# Power_MCU.net
KiCad netlist of a schematic drawn in Altium Designer
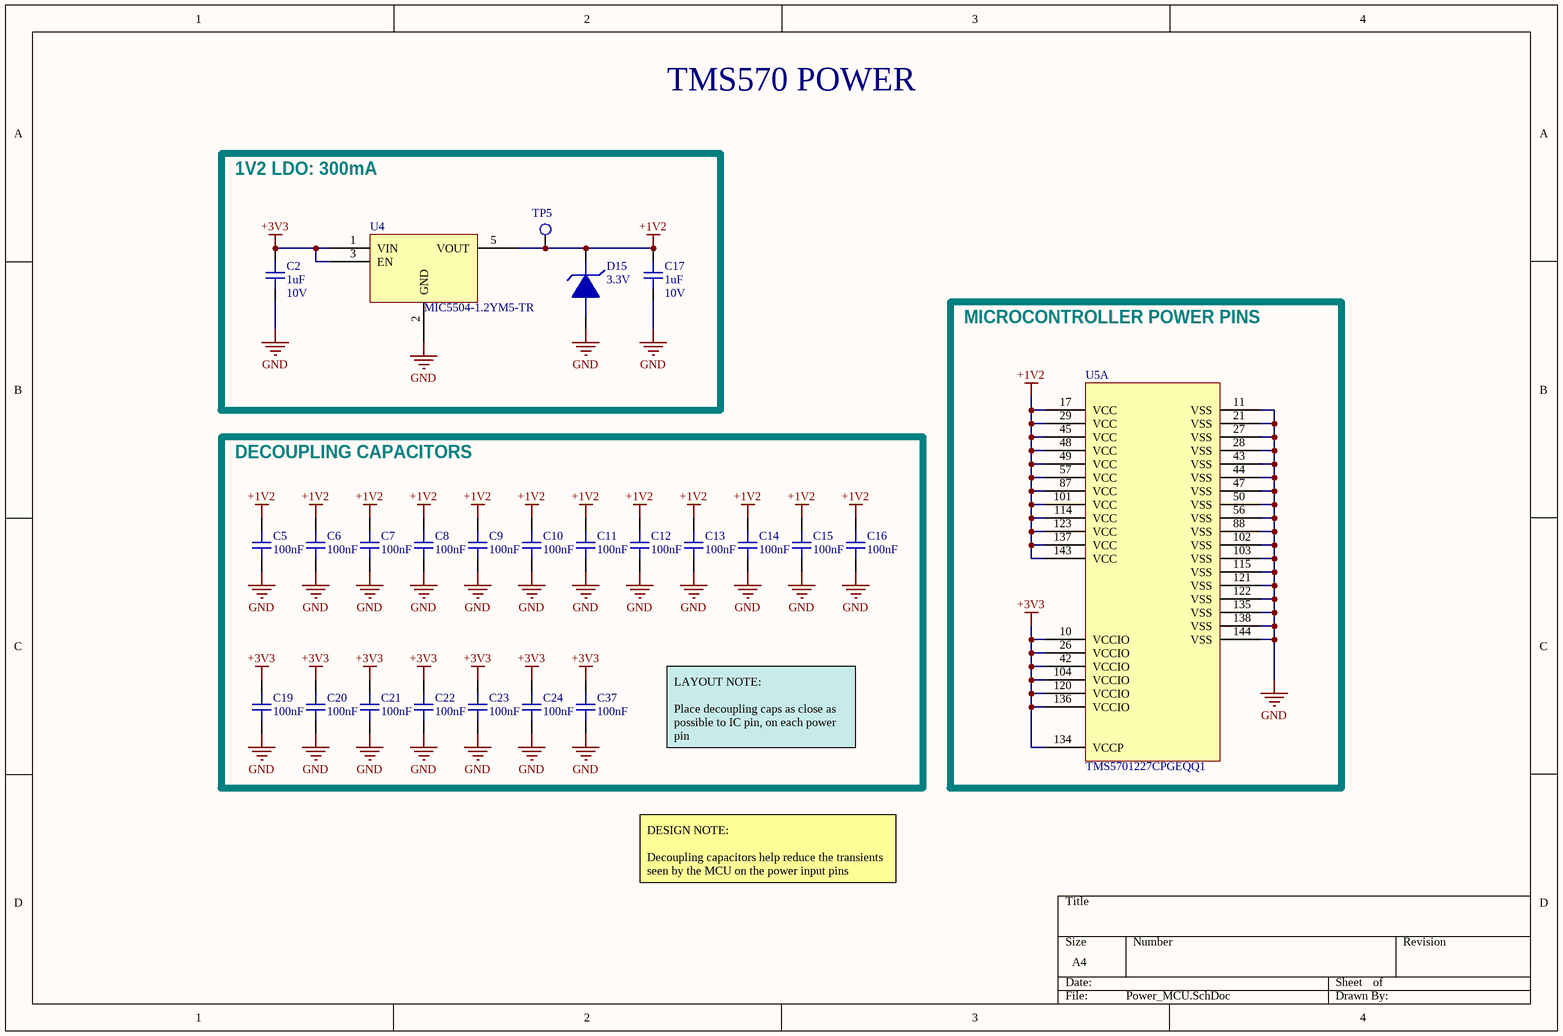
[diagram p0: Power_MCU.SchDoc]

(export (version "E")
  (design (tool "Eeschema 10.0.6"))
  (components
    (comp (ref "C2")
      (value "1uF")
      (footprint "C0402")
      (description "CAP MLCC 1uF 10V 0402 X5R 20% SMD 0402 85C Paper T/R")
      (fields
        (field (name "MANUFACTURER") "Samsung")
        (field (name "MANUFACTURER PART NUMBER") "CL05A105MP5NNNC")
        (field (name "VOLTAGE RATING") "10V")
      )
      (libsource (lib "PHANTOM_LIBRARY") (part "CL05A105MP5NNNC"))
    )
    (comp (ref "C5")
      (value "100nF")
      (footprint "C0402")
      (description "CAP MLCC 0.1uF 10V X5R 0402 20% SMD 0402 85C Paper T/R")
      (fields
        (field (name "MANUFACTURER") "Samsung")
        (field (name "MANUFACTURER PART NUMBER") "CL05A104MP5NNNC")
      )
      (libsource (lib "PHANTOM_LIBRARY") (part "CL05A104MP5NNNC"))
    )
    (comp (ref "C6")
      (value "100nF")
      (footprint "C0402")
      (description "CAP MLCC 0.1uF 10V X5R 0402 20% SMD 0402 85C Paper T/R")
      (fields
        (field (name "MANUFACTURER") "Samsung")
        (field (name "MANUFACTURER PART NUMBER") "CL05A104MP5NNNC")
      )
      (libsource (lib "PHANTOM_LIBRARY") (part "CL05A104MP5NNNC"))
    )
    (comp (ref "C7")
      (value "100nF")
      (footprint "C0402")
      (description "CAP MLCC 0.1uF 10V X5R 0402 20% SMD 0402 85C Paper T/R")
      (fields
        (field (name "MANUFACTURER") "Samsung")
        (field (name "MANUFACTURER PART NUMBER") "CL05A104MP5NNNC")
      )
      (libsource (lib "PHANTOM_LIBRARY") (part "CL05A104MP5NNNC"))
    )
    (comp (ref "C8")
      (value "100nF")
      (footprint "C0402")
      (description "CAP MLCC 0.1uF 10V X5R 0402 20% SMD 0402 85C Paper T/R")
      (fields
        (field (name "MANUFACTURER") "Samsung")
        (field (name "MANUFACTURER PART NUMBER") "CL05A104MP5NNNC")
      )
      (libsource (lib "PHANTOM_LIBRARY") (part "CL05A104MP5NNNC"))
    )
    (comp (ref "C9")
      (value "100nF")
      (footprint "C0402")
      (description "CAP MLCC 0.1uF 10V X5R 0402 20% SMD 0402 85C Paper T/R")
      (fields
        (field (name "MANUFACTURER") "Samsung")
        (field (name "MANUFACTURER PART NUMBER") "CL05A104MP5NNNC")
      )
      (libsource (lib "PHANTOM_LIBRARY") (part "CL05A104MP5NNNC"))
    )
    (comp (ref "C10")
      (value "100nF")
      (footprint "C0402")
      (description "CAP MLCC 0.1uF 10V X5R 0402 20% SMD 0402 85C Paper T/R")
      (fields
        (field (name "MANUFACTURER") "Samsung")
        (field (name "MANUFACTURER PART NUMBER") "CL05A104MP5NNNC")
      )
      (libsource (lib "PHANTOM_LIBRARY") (part "CL05A104MP5NNNC"))
    )
    (comp (ref "C11")
      (value "100nF")
      (footprint "C0402")
      (description "CAP MLCC 0.1uF 10V X5R 0402 20% SMD 0402 85C Paper T/R")
      (fields
        (field (name "MANUFACTURER") "Samsung")
        (field (name "MANUFACTURER PART NUMBER") "CL05A104MP5NNNC")
      )
      (libsource (lib "PHANTOM_LIBRARY") (part "CL05A104MP5NNNC"))
    )
    (comp (ref "C12")
      (value "100nF")
      (footprint "C0402")
      (description "CAP MLCC 0.1uF 10V X5R 0402 20% SMD 0402 85C Paper T/R")
      (fields
        (field (name "MANUFACTURER") "Samsung")
        (field (name "MANUFACTURER PART NUMBER") "CL05A104MP5NNNC")
      )
      (libsource (lib "PHANTOM_LIBRARY") (part "CL05A104MP5NNNC"))
    )
    (comp (ref "C13")
      (value "100nF")
      (footprint "C0402")
      (description "CAP MLCC 0.1uF 10V X5R 0402 20% SMD 0402 85C Paper T/R")
      (fields
        (field (name "MANUFACTURER") "Samsung")
        (field (name "MANUFACTURER PART NUMBER") "CL05A104MP5NNNC")
      )
      (libsource (lib "PHANTOM_LIBRARY") (part "CL05A104MP5NNNC"))
    )
    (comp (ref "C14")
      (value "100nF")
      (footprint "C0402")
      (description "CAP MLCC 0.1uF 10V X5R 0402 20% SMD 0402 85C Paper T/R")
      (fields
        (field (name "MANUFACTURER") "Samsung")
        (field (name "MANUFACTURER PART NUMBER") "CL05A104MP5NNNC")
      )
      (libsource (lib "PHANTOM_LIBRARY") (part "CL05A104MP5NNNC"))
    )
    (comp (ref "C15")
      (value "100nF")
      (footprint "C0402")
      (description "CAP MLCC 0.1uF 10V X5R 0402 20% SMD 0402 85C Paper T/R")
      (fields
        (field (name "MANUFACTURER") "Samsung")
        (field (name "MANUFACTURER PART NUMBER") "CL05A104MP5NNNC")
      )
      (libsource (lib "PHANTOM_LIBRARY") (part "CL05A104MP5NNNC"))
    )
    (comp (ref "C16")
      (value "100nF")
      (footprint "C0402")
      (description "CAP MLCC 0.1uF 10V X5R 0402 20% SMD 0402 85C Paper T/R")
      (fields
        (field (name "MANUFACTURER") "Samsung")
        (field (name "MANUFACTURER PART NUMBER") "CL05A104MP5NNNC")
      )
      (libsource (lib "PHANTOM_LIBRARY") (part "CL05A104MP5NNNC"))
    )
    (comp (ref "C17")
      (value "1uF")
      (footprint "C0402")
      (description "CAP MLCC 1uF 10V 0402 X5R 20% SMD 0402 85C Paper T/R")
      (fields
        (field (name "MANUFACTURER") "Samsung")
        (field (name "MANUFACTURER PART NUMBER") "CL05A105MP5NNNC")
        (field (name "VOLTAGE RATING") "10V")
      )
      (libsource (lib "PHANTOM_LIBRARY") (part "CL05A105MP5NNNC"))
    )
    (comp (ref "C19")
      (value "100nF")
      (footprint "C0402")
      (description "CAP MLCC 0.1uF 10V X5R 0402 20% SMD 0402 85C Paper T/R")
      (fields
        (field (name "MANUFACTURER") "Samsung")
        (field (name "MANUFACTURER PART NUMBER") "CL05A104MP5NNNC")
      )
      (libsource (lib "PHANTOM_LIBRARY") (part "CL05A104MP5NNNC"))
    )
    (comp (ref "C20")
      (value "100nF")
      (footprint "C0402")
      (description "CAP MLCC 0.1uF 10V X5R 0402 20% SMD 0402 85C Paper T/R")
      (fields
        (field (name "MANUFACTURER") "Samsung")
        (field (name "MANUFACTURER PART NUMBER") "CL05A104MP5NNNC")
      )
      (libsource (lib "PHANTOM_LIBRARY") (part "CL05A104MP5NNNC"))
    )
    (comp (ref "C21")
      (value "100nF")
      (footprint "C0402")
      (description "CAP MLCC 0.1uF 10V X5R 0402 20% SMD 0402 85C Paper T/R")
      (fields
        (field (name "MANUFACTURER") "Samsung")
        (field (name "MANUFACTURER PART NUMBER") "CL05A104MP5NNNC")
      )
      (libsource (lib "PHANTOM_LIBRARY") (part "CL05A104MP5NNNC"))
    )
    (comp (ref "C22")
      (value "100nF")
      (footprint "C0402")
      (description "CAP MLCC 0.1uF 10V X5R 0402 20% SMD 0402 85C Paper T/R")
      (fields
        (field (name "MANUFACTURER") "Samsung")
        (field (name "MANUFACTURER PART NUMBER") "CL05A104MP5NNNC")
      )
      (libsource (lib "PHANTOM_LIBRARY") (part "CL05A104MP5NNNC"))
    )
    (comp (ref "C23")
      (value "100nF")
      (footprint "C0402")
      (description "CAP MLCC 0.1uF 10V X5R 0402 20% SMD 0402 85C Paper T/R")
      (fields
        (field (name "MANUFACTURER") "Samsung")
        (field (name "MANUFACTURER PART NUMBER") "CL05A104MP5NNNC")
      )
      (libsource (lib "PHANTOM_LIBRARY") (part "CL05A104MP5NNNC"))
    )
    (comp (ref "C24")
      (value "100nF")
      (footprint "C0402")
      (description "CAP MLCC 0.1uF 10V X5R 0402 20% SMD 0402 85C Paper T/R")
      (fields
        (field (name "MANUFACTURER") "Samsung")
        (field (name "MANUFACTURER PART NUMBER") "CL05A104MP5NNNC")
      )
      (libsource (lib "PHANTOM_LIBRARY") (part "CL05A104MP5NNNC"))
    )
    (comp (ref "C37")
      (value "100nF")
      (footprint "C0402")
      (description "CAP MLCC 0.1uF 10V X5R 0402 20% SMD 0402 85C Paper T/R")
      (fields
        (field (name "MANUFACTURER") "Samsung")
        (field (name "MANUFACTURER PART NUMBER") "CL05A104MP5NNNC")
      )
      (libsource (lib "PHANTOM_LIBRARY") (part "CL05A104MP5NNNC"))
    )
    (comp (ref "D15")
      (value "3.3V")
      (footprint "DIODE_TVS")
      (description "DIODE ZENER 3.3V 1.5W SMA")
      (fields
        (field (name "MANUFACTURER") "ON Semiconductor")
        (field (name "MANUFACTURER PART NUMBER") "1SMA5913BT3G")
      )
      (libsource (lib "PHANTOM_LIBRARY") (part "1SMA5913BT3G"))
    )
    (comp (ref "TP5")
      (value "5015")
      (footprint "TP_HOOK")
      (description "TEST POINT, PCB, SMT")
      (fields (field (name "MANUFACTURER") "Keystone Electronics"))
      (libsource (lib "PHANTOM_LIBRARY") (part "5015"))
    )
    (comp (ref "U4")
      (value "MIC5504-1.2YM5-TR")
      (footprint "SOT23-5-MIC5504")
      (description "IC LDO 1.2V 300mA Enable Pull-Down & Auto Discharge, 5 SOT-23 T/R")
      (fields (field (name "MANUFACTURER") "Microchip"))
      (libsource (lib "PHANTOM_LIBRARY") (part "MIC5504-1.2YM5-TR"))
    )
    (comp (ref "U5")
      (value "TMS5701227CPGEQQ1")
      (footprint "LQFP-144")
      (description "IC MCU 16-Bit/32-Bit Hercules TMS570 ARM Cortex R4F RISC 1280KB Flash 1.2V/3.3V 144-Pin LQFP")
      (fields (field (name "MANUFACTURER") "Texas Instruments"))
      (libsource (lib "PHANTOM_LIBRARY") (part "TMS5701227CPGEQQ1"))
    )
  )
  (nets
    (net (code "1") (name "+1V2") (class "Default")
      (node (ref "C10") (pin "2") (pinfunction "2_2") (pintype "passive"))
      (node (ref "C11") (pin "2") (pinfunction "2_2") (pintype "passive"))
      (node (ref "C12") (pin "2") (pinfunction "2_2") (pintype "passive"))
      (node (ref "C13") (pin "2") (pinfunction "2_2") (pintype "passive"))
      (node (ref "C14") (pin "2") (pinfunction "2_2") (pintype "passive"))
      (node (ref "C15") (pin "2") (pinfunction "2_2") (pintype "passive"))
      (node (ref "C16") (pin "2") (pinfunction "2_2") (pintype "passive"))
      (node (ref "C17") (pin "2") (pinfunction "2_2") (pintype "passive"))
      (node (ref "C5") (pin "2") (pinfunction "2_2") (pintype "passive"))
      (node (ref "C6") (pin "2") (pinfunction "2_2") (pintype "passive"))
      (node (ref "C7") (pin "2") (pinfunction "2_2") (pintype "passive"))
      (node (ref "C8") (pin "2") (pinfunction "2_2") (pintype "passive"))
      (node (ref "C9") (pin "2") (pinfunction "2_2") (pintype "passive"))
      (node (ref "D15") (pin "1") (pinfunction "1_1") (pintype "passive"))
      (node (ref "TP5") (pin "1") (pinfunction "1_1") (pintype "passive"))
      (node (ref "U4") (pin "5") (pinfunction "VOUT_5") (pintype "passive"))
      (node (ref "U5") (pin "101") (pinfunction "VCC_101") (pintype "passive"))
      (node (ref "U5") (pin "114") (pinfunction "VCC_114") (pintype "passive"))
      (node (ref "U5") (pin "123") (pinfunction "VCC_123") (pintype "passive"))
      (node (ref "U5") (pin "137") (pinfunction "VCC_137") (pintype "passive"))
      (node (ref "U5") (pin "143") (pinfunction "VCC_143") (pintype "passive"))
      (node (ref "U5") (pin "17") (pinfunction "VCC_17") (pintype "passive"))
      (node (ref "U5") (pin "29") (pinfunction "VCC_29") (pintype "passive"))
      (node (ref "U5") (pin "45") (pinfunction "VCC_45") (pintype "passive"))
      (node (ref "U5") (pin "48") (pinfunction "VCC_48") (pintype "passive"))
      (node (ref "U5") (pin "49") (pinfunction "VCC_49") (pintype "passive"))
      (node (ref "U5") (pin "57") (pinfunction "VCC_57") (pintype "passive"))
      (node (ref "U5") (pin "87") (pinfunction "VCC_87") (pintype "passive"))
    )
    (net (code "2") (name "+3V3") (class "Default")
      (node (ref "C19") (pin "2") (pinfunction "2_2") (pintype "passive"))
      (node (ref "C2") (pin "2") (pinfunction "2_2") (pintype "passive"))
      (node (ref "C20") (pin "2") (pinfunction "2_2") (pintype "passive"))
      (node (ref "C21") (pin "2") (pinfunction "2_2") (pintype "passive"))
      (node (ref "C22") (pin "2") (pinfunction "2_2") (pintype "passive"))
      (node (ref "C23") (pin "2") (pinfunction "2_2") (pintype "passive"))
      (node (ref "C24") (pin "2") (pinfunction "2_2") (pintype "passive"))
      (node (ref "C37") (pin "2") (pinfunction "2_2") (pintype "passive"))
      (node (ref "U4") (pin "1") (pinfunction "VIN_1") (pintype "passive"))
      (node (ref "U4") (pin "3") (pinfunction "EN_3") (pintype "passive"))
      (node (ref "U5") (pin "10") (pinfunction "VCCIO_10") (pintype "passive"))
      (node (ref "U5") (pin "104") (pinfunction "VCCIO_104") (pintype "passive"))
      (node (ref "U5") (pin "120") (pinfunction "VCCIO_120") (pintype "passive"))
      (node (ref "U5") (pin "134") (pinfunction "VCCP_134") (pintype "passive"))
      (node (ref "U5") (pin "136") (pinfunction "VCCIO_136") (pintype "passive"))
      (node (ref "U5") (pin "26") (pinfunction "VCCIO_26") (pintype "passive"))
      (node (ref "U5") (pin "42") (pinfunction "VCCIO_42") (pintype "passive"))
    )
    (net (code "3") (name "GND") (class "Default")
      (node (ref "C10") (pin "1") (pinfunction "1_1") (pintype "passive"))
      (node (ref "C11") (pin "1") (pinfunction "1_1") (pintype "passive"))
      (node (ref "C12") (pin "1") (pinfunction "1_1") (pintype "passive"))
      (node (ref "C13") (pin "1") (pinfunction "1_1") (pintype "passive"))
      (node (ref "C14") (pin "1") (pinfunction "1_1") (pintype "passive"))
      (node (ref "C15") (pin "1") (pinfunction "1_1") (pintype "passive"))
      (node (ref "C16") (pin "1") (pinfunction "1_1") (pintype "passive"))
      (node (ref "C17") (pin "1") (pinfunction "1_1") (pintype "passive"))
      (node (ref "C19") (pin "1") (pinfunction "1_1") (pintype "passive"))
      (node (ref "C2") (pin "1") (pinfunction "1_1") (pintype "passive"))
      (node (ref "C20") (pin "1") (pinfunction "1_1") (pintype "passive"))
      (node (ref "C21") (pin "1") (pinfunction "1_1") (pintype "passive"))
      (node (ref "C22") (pin "1") (pinfunction "1_1") (pintype "passive"))
      (node (ref "C23") (pin "1") (pinfunction "1_1") (pintype "passive"))
      (node (ref "C24") (pin "1") (pinfunction "1_1") (pintype "passive"))
      (node (ref "C37") (pin "1") (pinfunction "1_1") (pintype "passive"))
      (node (ref "C5") (pin "1") (pinfunction "1_1") (pintype "passive"))
      (node (ref "C6") (pin "1") (pinfunction "1_1") (pintype "passive"))
      (node (ref "C7") (pin "1") (pinfunction "1_1") (pintype "passive"))
      (node (ref "C8") (pin "1") (pinfunction "1_1") (pintype "passive"))
      (node (ref "C9") (pin "1") (pinfunction "1_1") (pintype "passive"))
      (node (ref "D15") (pin "2") (pinfunction "2_2") (pintype "passive"))
      (node (ref "U4") (pin "2") (pinfunction "GND_2") (pintype "passive"))
      (node (ref "U5") (pin "102") (pinfunction "VSS_102") (pintype "passive"))
      (node (ref "U5") (pin "103") (pinfunction "VSS_103") (pintype "passive"))
      (node (ref "U5") (pin "11") (pinfunction "VSS_11") (pintype "passive"))
      (node (ref "U5") (pin "115") (pinfunction "VSS_115") (pintype "passive"))
      (node (ref "U5") (pin "121") (pinfunction "VSS_121") (pintype "passive"))
      (node (ref "U5") (pin "122") (pinfunction "VSS_122") (pintype "passive"))
      (node (ref "U5") (pin "135") (pinfunction "VSS_135") (pintype "passive"))
      (node (ref "U5") (pin "138") (pinfunction "VSS_138") (pintype "passive"))
      (node (ref "U5") (pin "144") (pinfunction "VSS_144") (pintype "passive"))
      (node (ref "U5") (pin "21") (pinfunction "VSS_21") (pintype "passive"))
      (node (ref "U5") (pin "27") (pinfunction "VSS_27") (pintype "passive"))
      (node (ref "U5") (pin "28") (pinfunction "VSS_28") (pintype "passive"))
      (node (ref "U5") (pin "43") (pinfunction "VSS_43") (pintype "passive"))
      (node (ref "U5") (pin "44") (pinfunction "VSS_44") (pintype "passive"))
      (node (ref "U5") (pin "47") (pinfunction "VSS_47") (pintype "passive"))
      (node (ref "U5") (pin "50") (pinfunction "VSS_50") (pintype "passive"))
      (node (ref "U5") (pin "56") (pinfunction "VSS_56") (pintype "passive"))
      (node (ref "U5") (pin "88") (pinfunction "VSS_88") (pintype "passive"))
    )
  )
)
